# LINEAR_POWER_SUPPLY_0-30V_v1.net
KiCad netlist of a schematic drawn in Altium Designer
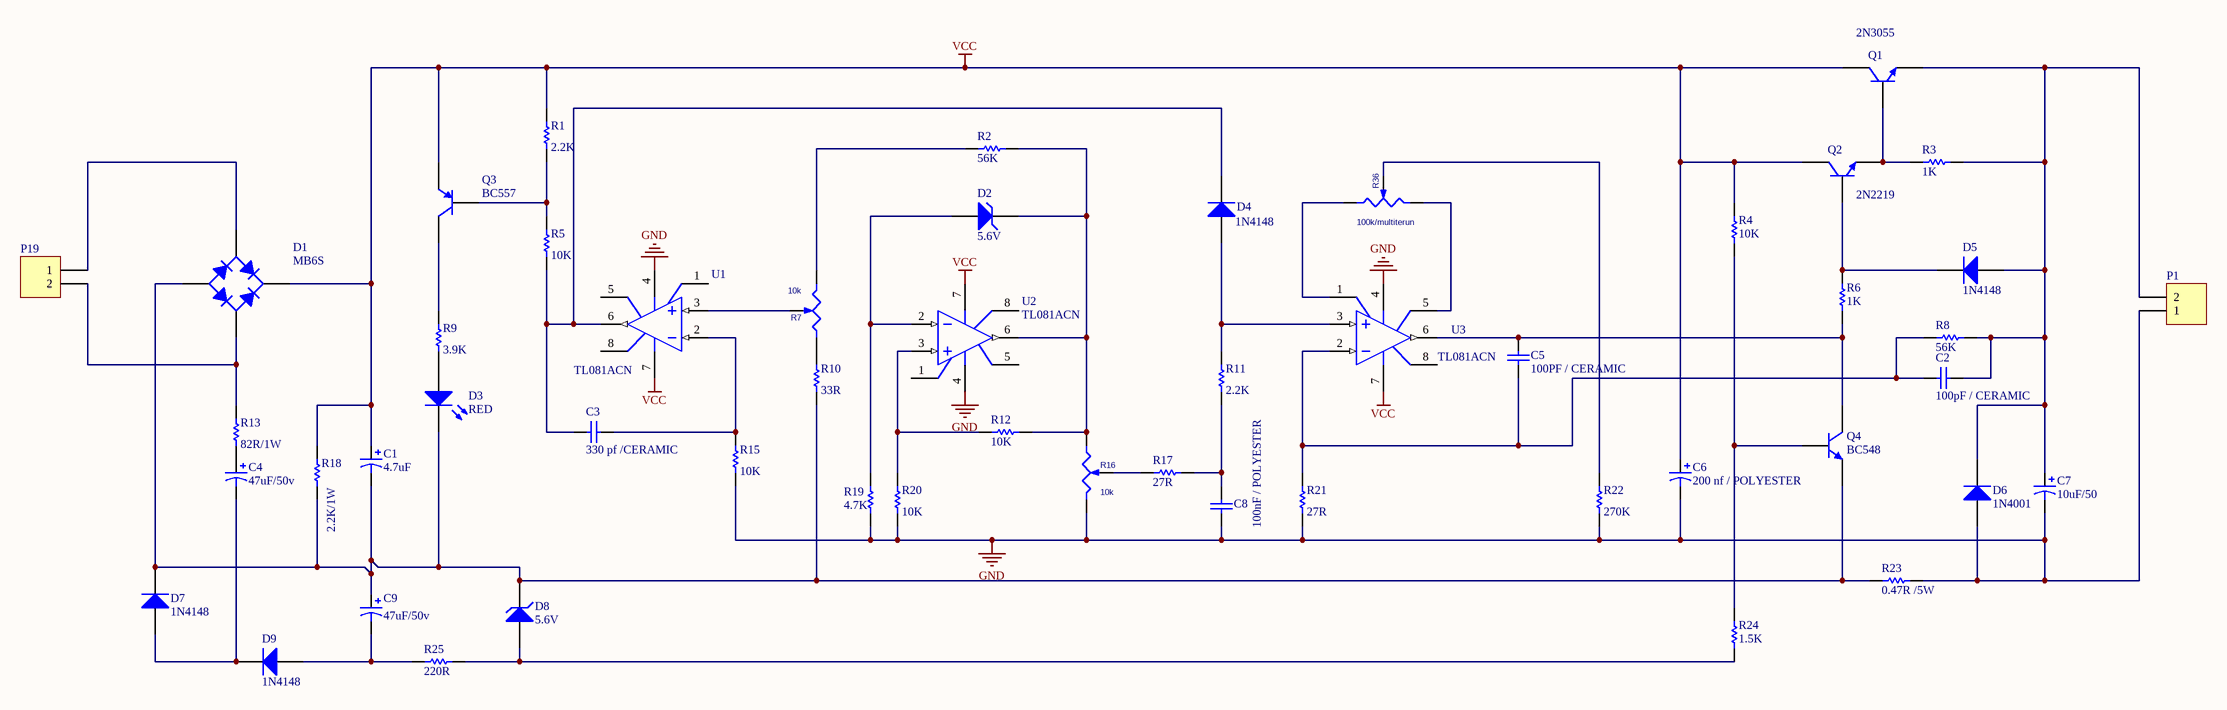
[diagram p0: LINEAR POWER SUPPLY 0-30V_v1.SchDoc]

(export (version "E")
  (design (tool "Eeschema 10.0.6"))
  (components
    (comp (ref "C1")
      (value "4.7uF")
      (footprint "Rad.1/.2-SMALL - duplicate")
      (description "Polarized Capacitor (Radial)")
      (fields (field (name "PUBLISHER") "Altium Limited"))
      (libsource (lib "Miscellaneous Devices") (part "Cap Pol1"))
    )
    (comp (ref "C2")
      (value "100pF / CERAMIC")
      (footprint "RAD-0.1_cap")
      (description "Capacitor")
      (fields (field (name "PUBLISHER") "Altium Limited"))
      (libsource (lib "Miscellaneous Devices") (part "Cap"))
    )
    (comp (ref "C3")
      (value "330 pf /CERAMIC")
      (footprint "RAD-0.1_cap")
      (description "Capacitor")
      (fields (field (name "PUBLISHER") "Altium Limited"))
      (libsource (lib "Miscellaneous Devices") (part "Cap"))
    )
    (comp (ref "C4")
      (value "47uF/50v")
      (footprint "Rad.1/.2-SMALL - duplicate")
      (description "Polarized Capacitor (Radial)")
      (fields (field (name "PUBLISHER") "Altium Limited"))
      (libsource (lib "Miscellaneous Devices") (part "Cap Pol1"))
    )
    (comp (ref "C5")
      (value "100PF / CERAMIC")
      (footprint "RAD-0.1_cap")
      (description "Capacitor")
      (fields (field (name "PUBLISHER") "Altium Limited"))
      (libsource (lib "Miscellaneous Devices") (part "Cap"))
    )
    (comp (ref "C6")
      (value "200 nf / POLYESTER")
      (footprint "Rad.1/.2-SMALL - duplicate")
      (description "Polarized Capacitor (Radial)")
      (fields (field (name "PUBLISHER") "Altium Limited"))
      (libsource (lib "Miscellaneous Devices") (part "Cap Pol1"))
    )
    (comp (ref "C7")
      (value "10uF/50")
      (footprint "Rad.1/.2-SMALL - duplicate")
      (description "Polarized Capacitor (Radial)")
      (fields (field (name "PUBLISHER") "Altium Limited"))
      (libsource (lib "Miscellaneous Devices") (part "Cap Pol1"))
    )
    (comp (ref "C8")
      (value "100nF / POLYESTER")
      (footprint "RAD-0.2- duplicate")
      (description "Capacitor")
      (fields (field (name "PUBLISHER") "Altium Limited"))
      (libsource (lib "Miscellaneous Devices") (part "Cap"))
    )
    (comp (ref "C9")
      (value "47uF/50v")
      (footprint "Rad.1/.2-SMALL - duplicate")
      (description "Polarized Capacitor (Radial)")
      (fields (field (name "PUBLISHER") "Altium Limited"))
      (libsource (lib "Miscellaneous Devices") (part "Cap Pol1"))
    )
    (comp (ref "D1")
      (value "MB6S")
      (footprint "Bridge")
      (description "Full Wave Diode Bridge")
      (fields (field (name "PUBLISHER") "Altium Limited"))
      (libsource (lib "Miscellaneous Devices") (part "Bridge1"))
    )
    (comp (ref "D2")
      (value "5.6V")
      (footprint "DIODE_ZENER.AXIAL0.3")
      (description "Zener Diode")
      (fields (field (name "PUBLISHER") "Altium Limited"))
      (libsource (lib "Miscellaneous Devices") (part "D Zener"))
    )
    (comp (ref "D3")
      (value "RED")
      (footprint "Led_3mil - RED")
      (description "Typical INFRARED GaAs LED")
      (fields (field (name "PUBLISHER") "Altium Limited"))
      (libsource (lib "Miscellaneous Devices") (part "LED0"))
    )
    (comp (ref "D4")
      (value "1N4148")
      (footprint "Dioad_1n400x_2")
      (description "1 Amp General Purpose Rectifier")
      (fields (field (name "PUBLISHER") "Altium Limited"))
      (libsource (lib "Miscellaneous Devices") (part "Diode 1N4007"))
    )
    (comp (ref "D5")
      (value "1N4148")
      (footprint "Dioad_1n400x_2")
      (description "1 Amp General Purpose Rectifier")
      (fields (field (name "PUBLISHER") "Altium Limited"))
      (libsource (lib "Miscellaneous Devices") (part "Diode 1N4007"))
    )
    (comp (ref "D6")
      (value "1N4001")
      (footprint "Dioad_1n400x_2")
      (description "1 Amp General Purpose Rectifier")
      (fields (field (name "PUBLISHER") "Altium Limited"))
      (libsource (lib "Miscellaneous Devices") (part "Diode 1N4007"))
    )
    (comp (ref "D7")
      (value "1N4148")
      (footprint "Dioad_1n400x_2")
      (description "1 Amp General Purpose Rectifier")
      (fields (field (name "PUBLISHER") "Altium Limited"))
      (libsource (lib "Miscellaneous Devices") (part "Diode 1N4007"))
    )
    (comp (ref "D8")
      (value "5.6V")
      (footprint "DIODE_ZENER.AXIAL0.3")
      (description "Zener Diode")
      (fields (field (name "PUBLISHER") "Altium Limited"))
      (libsource (lib "Miscellaneous Devices") (part "D Zener"))
    )
    (comp (ref "D9")
      (value "1N4148")
      (footprint "Dioad_1n400x_2")
      (description "1 Amp General Purpose Rectifier")
      (fields (field (name "PUBLISHER") "Altium Limited"))
      (libsource (lib "Miscellaneous Devices") (part "Diode 1N4007"))
    )
    (comp (ref "P1")
      (value "Blue Connector 1*2 -kf301")
      (footprint "Blue Connector 1*2 -kf301")
      (fields (field (name "PUBLISHER") "Altium Limited"))
      (libsource (lib "Miscellaneous Connectors") (part "Header 2H"))
    )
    (comp (ref "P19")
      (value "24VDC/3A")
      (footprint "Blue Connector 1*2 -kf301")
      (description "Blue Connector 1*2 -kf301")
      (fields (field (name "PUBLISHER") "Altium Limited"))
      (libsource (lib "") (part "Header 2H_1"))
    )
    (comp (ref "Q1")
      (value "2N3055")
      (footprint "Blue Connector 1*3 -kf301")
      (description "NPN General Purpose Amplifier")
      (fields (field (name "PUBLISHER") "Altium Limited"))
      (libsource (lib "Miscellaneous Devices") (part "2N3904"))
    )
    (comp (ref "Q2")
      (value "2N2219")
      (footprint "TO-92A")
      (description "NPN General Purpose Amplifier")
      (fields (field (name "PUBLISHER") "Altium Limited"))
      (libsource (lib "Miscellaneous Devices") (part "2N3904"))
    )
    (comp (ref "Q3")
      (value "BC557")
      (footprint "TO-92A")
      (description "PNP General Purpose Amplifier")
      (fields (field (name "PUBLISHER") "Altium Limited"))
      (libsource (lib "Miscellaneous Devices") (part "2N3906"))
    )
    (comp (ref "Q4")
      (value "BC548")
      (footprint "TO-92A")
      (description "NPN General Purpose Amplifier")
      (fields (field (name "PUBLISHER") "Altium Limited"))
      (libsource (lib "Miscellaneous Devices") (part "2N3904"))
    )
    (comp (ref "R1")
      (value "2.2K")
      (footprint "AXIAL0.4 - 1k")
      (description "Resistor")
      (fields (field (name "PUBLISHER") "Altium Limited"))
      (libsource (lib "Miscellaneous Devices") (part "Res1"))
    )
    (comp (ref "R2")
      (value "56K")
      (footprint "AXIAL0.4 - 1k")
      (description "Resistor")
      (fields (field (name "PUBLISHER") "Altium Limited"))
      (libsource (lib "Miscellaneous Devices") (part "Res1"))
    )
    (comp (ref "R3")
      (value "1K")
      (footprint "AXIAL0.4 - 1k")
      (description "Resistor")
      (fields (field (name "PUBLISHER") "Altium Limited"))
      (libsource (lib "Miscellaneous Devices") (part "Res1"))
    )
    (comp (ref "R4")
      (value "10K")
      (footprint "AXIAL0.4 - 1k")
      (description "Resistor")
      (fields (field (name "PUBLISHER") "Altium Limited"))
      (libsource (lib "Miscellaneous Devices") (part "Res1"))
    )
    (comp (ref "R5")
      (value "10K")
      (footprint "AXIAL0.4 - 1k")
      (description "Resistor")
      (fields (field (name "PUBLISHER") "Altium Limited"))
      (libsource (lib "Miscellaneous Devices") (part "Res1"))
    )
    (comp (ref "R6")
      (value "1K")
      (footprint "AXIAL0.4 - 1k")
      (description "Resistor")
      (fields (field (name "PUBLISHER") "Altium Limited"))
      (libsource (lib "Miscellaneous Devices") (part "Res1"))
    )
    (comp (ref "R7") (value "10k") (footprint "Blue Connector 1*3 -kf301") (libsource (lib "*") (part "POT")))
    (comp (ref "R8")
      (value "56K")
      (footprint "AXIAL0.4 - 1k")
      (description "Resistor")
      (fields (field (name "PUBLISHER") "Altium Limited"))
      (libsource (lib "Miscellaneous Devices") (part "Res1"))
    )
    (comp (ref "R9")
      (value "3.9K")
      (footprint "AXIAL0.4 - 1k")
      (description "Resistor")
      (fields (field (name "PUBLISHER") "Altium Limited"))
      (libsource (lib "Miscellaneous Devices") (part "Res1"))
    )
    (comp (ref "R10")
      (value "33R")
      (footprint "AXIAL0.4 - 1k")
      (description "Resistor")
      (fields (field (name "PUBLISHER") "Altium Limited"))
      (libsource (lib "Miscellaneous Devices") (part "Res1"))
    )
    (comp (ref "R11")
      (value "2.2K")
      (footprint "AXIAL0.4 - 1k")
      (description "Resistor")
      (fields (field (name "PUBLISHER") "Altium Limited"))
      (libsource (lib "Miscellaneous Devices") (part "Res1"))
    )
    (comp (ref "R12")
      (value "10K")
      (footprint "AXIAL0.4 - 1k")
      (description "Resistor")
      (fields (field (name "PUBLISHER") "Altium Limited"))
      (libsource (lib "Miscellaneous Devices") (part "Res1"))
    )
    (comp (ref "R13")
      (value "82R/1W")
      (footprint "AXIAL0.4 - 1k")
      (description "Resistor")
      (fields (field (name "PUBLISHER") "Altium Limited"))
      (libsource (lib "Miscellaneous Devices") (part "Res1"))
    )
    (comp (ref "R15")
      (value "10K")
      (footprint "AXIAL0.4 - 1k")
      (description "Resistor")
      (fields (field (name "PUBLISHER") "Altium Limited"))
      (libsource (lib "Miscellaneous Devices") (part "Res1"))
    )
    (comp (ref "R16")
      (value "10k")
      (footprint "Blue Connector 1*3 -kf301")
      (libsource (lib "*") (part "POT"))
    )
    (comp (ref "R17")
      (value "27R")
      (footprint "AXIAL0.4 - 1k")
      (description "Resistor")
      (fields (field (name "PUBLISHER") "Altium Limited"))
      (libsource (lib "Miscellaneous Devices") (part "Res1"))
    )
    (comp (ref "R18")
      (value "2.2K/1W")
      (footprint "AXIAL0.4 - 1k")
      (description "Resistor")
      (fields (field (name "PUBLISHER") "Altium Limited"))
      (libsource (lib "Miscellaneous Devices") (part "Res1"))
    )
    (comp (ref "R19")
      (value "4.7K")
      (footprint "AXIAL0.4 - 1k")
      (description "Resistor")
      (fields (field (name "PUBLISHER") "Altium Limited"))
      (libsource (lib "Miscellaneous Devices") (part "Res1"))
    )
    (comp (ref "R20")
      (value "10K")
      (footprint "AXIAL0.4 - 1k")
      (description "Resistor")
      (fields (field (name "PUBLISHER") "Altium Limited"))
      (libsource (lib "Miscellaneous Devices") (part "Res1"))
    )
    (comp (ref "R21")
      (value "27R")
      (footprint "AXIAL0.4 - 1k")
      (description "Resistor")
      (fields (field (name "PUBLISHER") "Altium Limited"))
      (libsource (lib "Miscellaneous Devices") (part "Res1"))
    )
    (comp (ref "R22")
      (value "270K")
      (footprint "AXIAL0.4 - 1k")
      (description "Resistor")
      (fields (field (name "PUBLISHER") "Altium Limited"))
      (libsource (lib "Miscellaneous Devices") (part "Res1"))
    )
    (comp (ref "R23")
      (value "0.47R /5W")
      (footprint "AXIAL0.4 - 1k")
      (description "Resistor")
      (fields (field (name "PUBLISHER") "Altium Limited"))
      (libsource (lib "Miscellaneous Devices") (part "Res1"))
    )
    (comp (ref "R24")
      (value "1.5K")
      (footprint "AXIAL0.4 - 1k")
      (description "Resistor")
      (fields (field (name "PUBLISHER") "Altium Limited"))
      (libsource (lib "Miscellaneous Devices") (part "Res1"))
    )
    (comp (ref "R25")
      (value "220R")
      (footprint "AXIAL0.4 - 1k")
      (description "Resistor")
      (fields (field (name "PUBLISHER") "Altium Limited"))
      (libsource (lib "Miscellaneous Devices") (part "Res1"))
    )
    (comp (ref "R36") (value "100k/multiterun") (footprint "MULTITERN") (libsource (lib "*") (part "POT")))
    (comp (ref "U1")
      (value "TL081ACN")
      (footprint "DIP8")
      (description "General-Purpose J-FET Single Operational Amplifier")
      (fields (field (name "PUBLISHER") "Altium Limited"))
      (libsource (lib "ST Operational Amplifier") (part "TL081ACN"))
    )
    (comp (ref "U2")
      (value "TL081ACN")
      (footprint "DIP8")
      (description "General-Purpose J-FET Single Operational Amplifier")
      (fields (field (name "PUBLISHER") "Altium Limited"))
      (libsource (lib "ST Operational Amplifier") (part "TL081ACN"))
    )
    (comp (ref "U3")
      (value "TL081ACN")
      (footprint "DIP8")
      (description "General-Purpose J-FET Single Operational Amplifier")
      (fields (field (name "PUBLISHER") "Altium Limited"))
      (libsource (lib "ST Operational Amplifier") (part "TL081ACN"))
    )
  )
  (nets
    (net (code "1") (name "GND") (class "Default")
      (node (ref "C6") (pin "2") (pintype "passive"))
      (node (ref "C7") (pin "2") (pintype "passive"))
      (node (ref "C8") (pin "1") (pinfunction "1_1") (pintype "passive"))
      (node (ref "D6") (pin "1") (pinfunction "A_1") (pintype "passive"))
      (node (ref "P1") (pin "1") (pinfunction "1_1") (pintype "passive"))
      (node (ref "R15") (pin "1") (pinfunction "1_1") (pintype "passive"))
      (node (ref "R16") (pin "1") (pinfunction "A_1") (pintype "passive"))
      (node (ref "R19") (pin "2") (pinfunction "2_2") (pintype "passive"))
      (node (ref "R20") (pin "1") (pinfunction "1_1") (pintype "passive"))
      (node (ref "R21") (pin "1") (pinfunction "1_1") (pintype "passive"))
      (node (ref "R22") (pin "1") (pinfunction "1_1") (pintype "passive"))
      (node (ref "R23") (pin "1") (pinfunction "1_1") (pintype "passive"))
      (node (ref "U1") (pin "4") (pinfunction "V-_4") (pintype "power_in"))
      (node (ref "U2") (pin "4") (pinfunction "V-_4") (pintype "power_in"))
      (node (ref "U3") (pin "4") (pinfunction "V-_4") (pintype "power_in"))
    )
    (net (code "2") (name "Net-(C4-Pad1)") (class "Default")
      (node (ref "C4") (pin "1") (pintype "passive"))
      (node (ref "R13") (pin "1") (pinfunction "1_1") (pintype "passive"))
    )
    (net (code "3") (name "Net-(C8-Pad2)") (class "Default")
      (node (ref "C8") (pin "2") (pinfunction "2_2") (pintype "passive"))
      (node (ref "R11") (pin "1") (pinfunction "1_1") (pintype "passive"))
      (node (ref "R17") (pin "1") (pinfunction "1_1") (pintype "passive"))
    )
    (net (code "4") (name "Net-(D1-A)") (class "Default")
      (node (ref "C1") (pin "2") (pintype "passive"))
      (node (ref "C9") (pin "1") (pintype "passive"))
      (node (ref "D1") (pin "3") (pinfunction "A_3") (pintype "passive"))
      (node (ref "D3") (pin "2") (pinfunction "K_2") (pintype "passive"))
      (node (ref "D7") (pin "2") (pinfunction "K_2") (pintype "passive"))
      (node (ref "D8") (pin "K") (pinfunction "K_K") (pintype "passive"))
      (node (ref "Q4") (pin "1") (pinfunction "E_1") (pintype "passive"))
      (node (ref "R10") (pin "1") (pinfunction "1_1") (pintype "passive"))
      (node (ref "R18") (pin "1") (pinfunction "1_1") (pintype "passive"))
      (node (ref "R23") (pin "2") (pinfunction "2_2") (pintype "passive"))
    )
    (net (code "5") (name "Net-(D1-C-Pad2)") (class "Default")
      (node (ref "D1") (pin "2") (pinfunction "C_2") (pintype "passive"))
      (node (ref "P19") (pin "2") (pinfunction "2_2") (pintype "passive"))
      (node (ref "R13") (pin "2") (pinfunction "2_2") (pintype "passive"))
    )
    (net (code "6") (name "Net-(D1-C-Pad4)") (class "Default")
      (node (ref "D1") (pin "4") (pinfunction "C_4") (pintype "passive"))
      (node (ref "P19") (pin "1") (pinfunction "1_1") (pintype "passive"))
    )
    (net (code "7") (name "Net-(D3-A)") (class "Default")
      (node (ref "D3") (pin "1") (pinfunction "A_1") (pintype "passive"))
      (node (ref "R9") (pin "1") (pinfunction "1_1") (pintype "passive"))
    )
    (net (code "8") (name "Net-(D4-A)") (class "Default")
      (node (ref "D4") (pin "1") (pinfunction "A_1") (pintype "passive"))
      (node (ref "R11") (pin "2") (pinfunction "2_2") (pintype "passive"))
      (node (ref "U3") (pin "3") (pinfunction "IN+_3") (pintype "input"))
    )
    (net (code "9") (name "Net-(D4-K)") (class "Default")
      (node (ref "C3") (pin "2") (pinfunction "2_2") (pintype "passive"))
      (node (ref "D4") (pin "2") (pinfunction "K_2") (pintype "passive"))
      (node (ref "R5") (pin "1") (pinfunction "1_1") (pintype "passive"))
      (node (ref "U1") (pin "6") (pinfunction "OUT_6") (pintype "output"))
    )
    (net (code "10") (name "Net-(D5-A)") (class "Default")
      (node (ref "C2") (pin "1") (pinfunction "1_1") (pintype "passive"))
      (node (ref "C7") (pin "1") (pintype "passive"))
      (node (ref "D5") (pin "1") (pinfunction "A_1") (pintype "passive"))
      (node (ref "D6") (pin "2") (pinfunction "K_2") (pintype "passive"))
      (node (ref "P1") (pin "2") (pinfunction "2_2") (pintype "passive"))
      (node (ref "Q1") (pin "1") (pinfunction "E_1") (pintype "passive"))
      (node (ref "R3") (pin "2") (pinfunction "2_2") (pintype "passive"))
      (node (ref "R8") (pin "2") (pinfunction "2_2") (pintype "passive"))
    )
    (net (code "11") (name "Net-(D5-K)") (class "Default")
      (node (ref "D5") (pin "2") (pinfunction "K_2") (pintype "passive"))
      (node (ref "Q2") (pin "2") (pinfunction "B_2") (pintype "passive"))
      (node (ref "R6") (pin "1") (pinfunction "1_1") (pintype "passive"))
    )
    (net (code "12") (name "Net-(D7-A)") (class "Default")
      (node (ref "C4") (pin "2") (pintype "passive"))
      (node (ref "D7") (pin "1") (pinfunction "A_1") (pintype "passive"))
      (node (ref "D9") (pin "2") (pinfunction "K_2") (pintype "passive"))
    )
    (net (code "13") (name "Net-(D8-PadA)") (class "Default")
      (node (ref "D8") (pin "A") (pinfunction "A_A") (pintype "passive"))
      (node (ref "R24") (pin "2") (pinfunction "2_2") (pintype "passive"))
      (node (ref "R25") (pin "1") (pinfunction "1_1") (pintype "passive"))
    )
    (net (code "14") (name "Net-(D9-A)") (class "Default")
      (node (ref "C9") (pin "2") (pintype "passive"))
      (node (ref "D9") (pin "1") (pinfunction "A_1") (pintype "passive"))
      (node (ref "R25") (pin "2") (pinfunction "2_2") (pintype "passive"))
    )
    (net (code "15") (name "Net-(Q1-B)") (class "Default")
      (node (ref "Q1") (pin "2") (pinfunction "B_2") (pintype "passive"))
      (node (ref "Q2") (pin "1") (pinfunction "E_1") (pintype "passive"))
      (node (ref "R3") (pin "1") (pinfunction "1_1") (pintype "passive"))
    )
    (net (code "16") (name "Net-(Q3-B)") (class "Default")
      (node (ref "Q3") (pin "2") (pinfunction "B_2") (pintype "passive"))
      (node (ref "R1") (pin "1") (pinfunction "1_1") (pintype "passive"))
      (node (ref "R5") (pin "2") (pinfunction "2_2") (pintype "passive"))
    )
    (net (code "17") (name "Net-(Q3-C)") (class "Default")
      (node (ref "Q3") (pin "3") (pinfunction "C_3") (pintype "passive"))
      (node (ref "R9") (pin "2") (pinfunction "2_2") (pintype "passive"))
    )
    (net (code "18") (name "Net-(Q4-B)") (class "Default")
      (node (ref "Q4") (pin "2") (pinfunction "B_2") (pintype "passive"))
      (node (ref "R24") (pin "1") (pinfunction "1_1") (pintype "passive"))
      (node (ref "R4") (pin "2") (pinfunction "2_2") (pintype "passive"))
    )
    (net (code "19") (name "Net-(Q4-C)") (class "Default")
      (node (ref "C5") (pin "2") (pinfunction "2_2") (pintype "passive"))
      (node (ref "Q4") (pin "3") (pinfunction "C_3") (pintype "passive"))
      (node (ref "R6") (pin "2") (pinfunction "2_2") (pintype "passive"))
      (node (ref "U3") (pin "6") (pinfunction "OUT_6") (pintype "output"))
    )
    (net (code "20") (name "Net-(R7-A)") (class "Default")
      (node (ref "R2") (pin "2") (pinfunction "2_2") (pintype "passive"))
      (node (ref "R7") (pin "1") (pinfunction "A_1") (pintype "passive"))
    )
    (net (code "21") (name "Net-(R7-B)") (class "Default")
      (node (ref "R10") (pin "2") (pinfunction "2_2") (pintype "passive"))
      (node (ref "R7") (pin "3") (pinfunction "B_3") (pintype "passive"))
    )
    (net (code "22") (name "Net-(R7-WIPER)") (class "Default")
      (node (ref "R7") (pin "2") (pinfunction "WIPER_2") (pintype "passive"))
      (node (ref "U1") (pin "3") (pinfunction "IN+_3") (pintype "input"))
    )
    (net (code "23") (name "Net-(R16-B)") (class "Default")
      (node (ref "D2") (pin "K") (pinfunction "K_K") (pintype "passive"))
      (node (ref "R12") (pin "1") (pinfunction "1_1") (pintype "passive"))
      (node (ref "R16") (pin "3") (pinfunction "B_3") (pintype "passive"))
      (node (ref "R2") (pin "1") (pinfunction "1_1") (pintype "passive"))
      (node (ref "U2") (pin "6") (pinfunction "OUT_6") (pintype "output"))
    )
    (net (code "24") (name "Net-(R16-WIPER)") (class "Default")
      (node (ref "R16") (pin "2") (pinfunction "WIPER_2") (pintype "passive"))
      (node (ref "R17") (pin "2") (pinfunction "2_2") (pintype "passive"))
    )
    (net (code "25") (name "Net-(R36-A)") (class "Default")
      (node (ref "R36") (pin "1") (pinfunction "A_1") (pintype "passive"))
      (node (ref "U3") (pin "5") (pinfunction "OS_NULL_5") (pintype "passive"))
    )
    (net (code "26") (name "Net-(R36-B)") (class "Default")
      (node (ref "R36") (pin "3") (pinfunction "B_3") (pintype "passive"))
      (node (ref "U3") (pin "1") (pinfunction "OS_NULL_1") (pintype "passive"))
    )
    (net (code "27") (name "Net-(R36-WIPER)") (class "Default")
      (node (ref "R22") (pin "2") (pinfunction "2_2") (pintype "passive"))
      (node (ref "R36") (pin "2") (pinfunction "WIPER_2") (pintype "passive"))
    )
    (net (code "28") (name "Net-(U1-IN-)") (class "Default")
      (node (ref "C3") (pin "1") (pinfunction "1_1") (pintype "passive"))
      (node (ref "R15") (pin "2") (pinfunction "2_2") (pintype "passive"))
      (node (ref "U1") (pin "2") (pinfunction "IN-_2") (pintype "input"))
    )
    (net (code "29") (name "Net-(U2-IN+)") (class "Default")
      (node (ref "R12") (pin "2") (pinfunction "2_2") (pintype "passive"))
      (node (ref "R20") (pin "2") (pinfunction "2_2") (pintype "passive"))
      (node (ref "U2") (pin "3") (pinfunction "IN+_3") (pintype "input"))
    )
    (net (code "30") (name "Net-(U2-IN-)") (class "Default")
      (node (ref "D2") (pin "A") (pinfunction "A_A") (pintype "passive"))
      (node (ref "R19") (pin "1") (pinfunction "1_1") (pintype "passive"))
      (node (ref "U2") (pin "2") (pinfunction "IN-_2") (pintype "input"))
    )
    (net (code "31") (name "Net-(U3-IN-)") (class "Default")
      (node (ref "C2") (pin "2") (pinfunction "2_2") (pintype "passive"))
      (node (ref "C5") (pin "1") (pinfunction "1_1") (pintype "passive"))
      (node (ref "R21") (pin "2") (pinfunction "2_2") (pintype "passive"))
      (node (ref "R8") (pin "1") (pinfunction "1_1") (pintype "passive"))
      (node (ref "U3") (pin "2") (pinfunction "IN-_2") (pintype "input"))
    )
    (net (code "32") (name "VCC") (class "Default")
      (node (ref "C1") (pin "1") (pintype "passive"))
      (node (ref "C6") (pin "1") (pintype "passive"))
      (node (ref "D1") (pin "1") (pinfunction "K_1") (pintype "passive"))
      (node (ref "Q1") (pin "3") (pinfunction "C_3") (pintype "passive"))
      (node (ref "Q2") (pin "3") (pinfunction "C_3") (pintype "passive"))
      (node (ref "Q3") (pin "1") (pinfunction "E_1") (pintype "passive"))
      (node (ref "R1") (pin "2") (pinfunction "2_2") (pintype "passive"))
      (node (ref "R18") (pin "2") (pinfunction "2_2") (pintype "passive"))
      (node (ref "R4") (pin "1") (pinfunction "1_1") (pintype "passive"))
      (node (ref "U1") (pin "7") (pinfunction "V+_7") (pintype "power_in"))
      (node (ref "U2") (pin "7") (pinfunction "V+_7") (pintype "power_in"))
      (node (ref "U3") (pin "7") (pinfunction "V+_7") (pintype "power_in"))
    )
    (net (code "33") (name "unconnected-(U1-NC-Pad8)") (class "Default")
      (node (ref "U1") (pin "8") (pinfunction "NC_8") (pintype "passive"))
    )
    (net (code "34") (name "unconnected-(U1-OS_NULL-Pad1)") (class "Default")
      (node (ref "U1") (pin "1") (pinfunction "OS_NULL_1") (pintype "passive"))
    )
    (net (code "35") (name "unconnected-(U1-OS_NULL-Pad5)") (class "Default")
      (node (ref "U1") (pin "5") (pinfunction "OS_NULL_5") (pintype "passive"))
    )
    (net (code "36") (name "unconnected-(U2-NC-Pad8)") (class "Default")
      (node (ref "U2") (pin "8") (pinfunction "NC_8") (pintype "passive"))
    )
    (net (code "37") (name "unconnected-(U2-OS_NULL-Pad1)") (class "Default")
      (node (ref "U2") (pin "1") (pinfunction "OS_NULL_1") (pintype "passive"))
    )
    (net (code "38") (name "unconnected-(U2-OS_NULL-Pad5)") (class "Default")
      (node (ref "U2") (pin "5") (pinfunction "OS_NULL_5") (pintype "passive"))
    )
    (net (code "39") (name "unconnected-(U3-NC-Pad8)") (class "Default")
      (node (ref "U3") (pin "8") (pinfunction "NC_8") (pintype "passive"))
    )
  )
)
